# Sheet1.net
KiCad netlist of a schematic drawn in Altium Designer
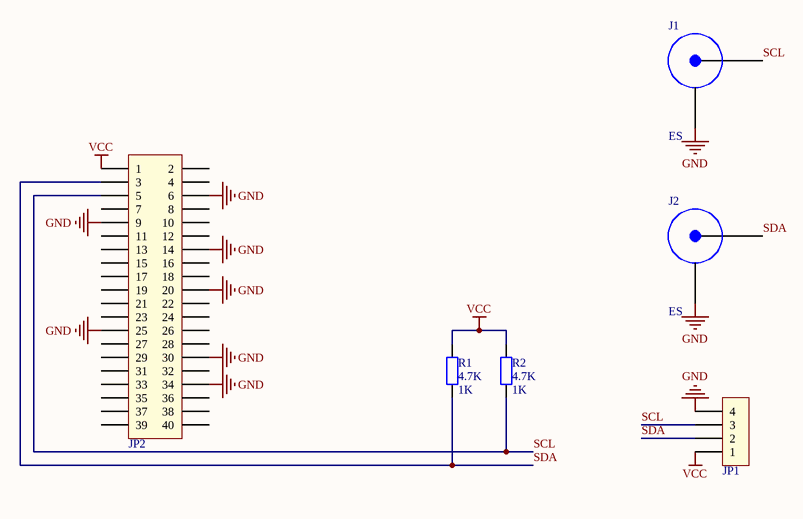
[diagram p0: Sheet1.SchDoc]

(export (version "E")
  (design (tool "Eeschema 10.0.6"))
  (components
    (comp (ref "J1") (value "ES") (footprint "BNC") (libsource (lib "Gamel_Trophy_v4re1") (part "BNC")))
    (comp (ref "J2") (value "ES") (footprint "BNC") (libsource (lib "Gamel_Trophy_v4re1") (part "BNC")))
    (comp (ref "JP1")
      (value "Connecteur Autocom 4pts")
      (footprint "Autocom HE14 - 4 - Coudé")
      (description "connecteur autocom HE14 4 pts")
      (fields
        (field (name "MANUFACTURER") "TE CONNECTIVITY / AMP")
        (field (name "MANUFACTURER PART NUMBER") "281698-4")
      )
      (libsource (lib "GEII") (part "Connecteur Autocom 4 pts"))
    )
    (comp (ref "JP2")
      (value "HE10 2x20")
      (footprint "HE10 2x20")
      (description "Header, 20-Pin, Dual row")
      (fields
        (field (name "MANUFACTURER") "HARTING")
        (field (name "MANUFACTURER PART NUMBER") "09 18 540 7324")
        (field (name "APPROVAL BODIES") "BT 224, BS 9525, F0023, NFC93-428 (HE10), MIL-C-83503, DIN 41651")
      )
      (libsource (lib "GEII") (part "HE10 2x20"))
    )
    (comp (ref "R1")
      (value "4.7K")
      (footprint "AXIAL-0.4")
      (description "Resistor")
      (fields (field (name "ALTIUM_VALUE") "1K") (field (name "PUBLISHER") "Altium Limited"))
      (libsource (lib "Miscellaneous Devices") (part "Res2"))
    )
    (comp (ref "R2")
      (value "4.7K")
      (footprint "AXIAL-0.4")
      (description "Resistor")
      (fields (field (name "ALTIUM_VALUE") "1K") (field (name "PUBLISHER") "Altium Limited"))
      (libsource (lib "Miscellaneous Devices") (part "Res2"))
    )
  )
  (nets
    (net (code "1") (name "/SCL") (class "Default")
      (node (ref "J1") (pin "1") (pinfunction "SIGNAL_1") (pintype "passive"))
      (node (ref "JP1") (pin "3") (pinfunction "3_3") (pintype "passive"))
      (node (ref "JP2") (pin "5") (pinfunction "5_5") (pintype "passive"))
      (node (ref "R2") (pin "1") (pinfunction "1_1") (pintype "passive"))
    )
    (net (code "2") (name "/SDA") (class "Default")
      (node (ref "J2") (pin "1") (pinfunction "SIGNAL_1") (pintype "passive"))
      (node (ref "JP1") (pin "2") (pinfunction "2_2") (pintype "passive"))
      (node (ref "JP2") (pin "3") (pinfunction "3_3") (pintype "passive"))
      (node (ref "R1") (pin "1") (pinfunction "1_1") (pintype "passive"))
    )
    (net (code "3") (name "GND") (class "Default")
      (node (ref "J1") (pin "2") (pinfunction "GND_2") (pintype "passive"))
      (node (ref "J2") (pin "2") (pinfunction "GND_2") (pintype "passive"))
      (node (ref "JP1") (pin "4") (pinfunction "4_4") (pintype "passive"))
      (node (ref "JP2") (pin "14") (pinfunction "14_14") (pintype "passive"))
      (node (ref "JP2") (pin "20") (pinfunction "20_20") (pintype "passive"))
      (node (ref "JP2") (pin "25") (pinfunction "25_25") (pintype "passive"))
      (node (ref "JP2") (pin "30") (pinfunction "30_30") (pintype "passive"))
      (node (ref "JP2") (pin "34") (pinfunction "34_34") (pintype "passive"))
      (node (ref "JP2") (pin "6") (pinfunction "6_6") (pintype "passive"))
      (node (ref "JP2") (pin "9") (pinfunction "9_9") (pintype "passive"))
    )
    (net (code "4") (name "VCC") (class "Default")
      (node (ref "JP1") (pin "1") (pinfunction "1_1") (pintype "passive"))
      (node (ref "JP2") (pin "1") (pinfunction "1_1") (pintype "passive"))
      (node (ref "R1") (pin "2") (pinfunction "2_2") (pintype "passive"))
      (node (ref "R2") (pin "2") (pinfunction "2_2") (pintype "passive"))
    )
    (net (code "5") (name "unconnected-(JP2-Pad2)") (class "Default")
      (node (ref "JP2") (pin "2") (pinfunction "2_2") (pintype "passive"))
    )
    (net (code "6") (name "unconnected-(JP2-Pad4)") (class "Default")
      (node (ref "JP2") (pin "4") (pinfunction "4_4") (pintype "passive"))
    )
    (net (code "7") (name "unconnected-(JP2-Pad7)") (class "Default")
      (node (ref "JP2") (pin "7") (pinfunction "7_7") (pintype "passive"))
    )
    (net (code "8") (name "unconnected-(JP2-Pad8)") (class "Default")
      (node (ref "JP2") (pin "8") (pinfunction "8_8") (pintype "passive"))
    )
    (net (code "9") (name "unconnected-(JP2-Pad10)") (class "Default")
      (node (ref "JP2") (pin "10") (pinfunction "10_10") (pintype "passive"))
    )
    (net (code "10") (name "unconnected-(JP2-Pad11)") (class "Default")
      (node (ref "JP2") (pin "11") (pinfunction "11_11") (pintype "passive"))
    )
    (net (code "11") (name "unconnected-(JP2-Pad12)") (class "Default")
      (node (ref "JP2") (pin "12") (pinfunction "12_12") (pintype "passive"))
    )
    (net (code "12") (name "unconnected-(JP2-Pad13)") (class "Default")
      (node (ref "JP2") (pin "13") (pinfunction "13_13") (pintype "passive"))
    )
    (net (code "13") (name "unconnected-(JP2-Pad15)") (class "Default")
      (node (ref "JP2") (pin "15") (pinfunction "15_15") (pintype "passive"))
    )
    (net (code "14") (name "unconnected-(JP2-Pad16)") (class "Default")
      (node (ref "JP2") (pin "16") (pinfunction "16_16") (pintype "passive"))
    )
    (net (code "15") (name "unconnected-(JP2-Pad17)") (class "Default")
      (node (ref "JP2") (pin "17") (pinfunction "17_17") (pintype "passive"))
    )
    (net (code "16") (name "unconnected-(JP2-Pad18)") (class "Default")
      (node (ref "JP2") (pin "18") (pinfunction "18_18") (pintype "passive"))
    )
    (net (code "17") (name "unconnected-(JP2-Pad19)") (class "Default")
      (node (ref "JP2") (pin "19") (pinfunction "19_19") (pintype "passive"))
    )
    (net (code "18") (name "unconnected-(JP2-Pad21)") (class "Default")
      (node (ref "JP2") (pin "21") (pinfunction "21_21") (pintype "passive"))
    )
    (net (code "19") (name "unconnected-(JP2-Pad22)") (class "Default")
      (node (ref "JP2") (pin "22") (pinfunction "22_22") (pintype "passive"))
    )
    (net (code "20") (name "unconnected-(JP2-Pad23)") (class "Default")
      (node (ref "JP2") (pin "23") (pinfunction "23_23") (pintype "passive"))
    )
    (net (code "21") (name "unconnected-(JP2-Pad24)") (class "Default")
      (node (ref "JP2") (pin "24") (pinfunction "24_24") (pintype "passive"))
    )
    (net (code "22") (name "unconnected-(JP2-Pad26)") (class "Default")
      (node (ref "JP2") (pin "26") (pinfunction "26_26") (pintype "passive"))
    )
    (net (code "23") (name "unconnected-(JP2-Pad27)") (class "Default")
      (node (ref "JP2") (pin "27") (pinfunction "27_27") (pintype "passive"))
    )
    (net (code "24") (name "unconnected-(JP2-Pad28)") (class "Default")
      (node (ref "JP2") (pin "28") (pinfunction "28_28") (pintype "passive"))
    )
    (net (code "25") (name "unconnected-(JP2-Pad29)") (class "Default")
      (node (ref "JP2") (pin "29") (pinfunction "29_29") (pintype "passive"))
    )
    (net (code "26") (name "unconnected-(JP2-Pad31)") (class "Default")
      (node (ref "JP2") (pin "31") (pinfunction "31_31") (pintype "passive"))
    )
    (net (code "27") (name "unconnected-(JP2-Pad32)") (class "Default")
      (node (ref "JP2") (pin "32") (pinfunction "32_32") (pintype "passive"))
    )
    (net (code "28") (name "unconnected-(JP2-Pad33)") (class "Default")
      (node (ref "JP2") (pin "33") (pinfunction "33_33") (pintype "passive"))
    )
    (net (code "29") (name "unconnected-(JP2-Pad35)") (class "Default")
      (node (ref "JP2") (pin "35") (pinfunction "35_35") (pintype "passive"))
    )
    (net (code "30") (name "unconnected-(JP2-Pad36)") (class "Default")
      (node (ref "JP2") (pin "36") (pinfunction "36_36") (pintype "passive"))
    )
    (net (code "31") (name "unconnected-(JP2-Pad37)") (class "Default")
      (node (ref "JP2") (pin "37") (pinfunction "37_37") (pintype "passive"))
    )
    (net (code "32") (name "unconnected-(JP2-Pad38)") (class "Default")
      (node (ref "JP2") (pin "38") (pinfunction "38_38") (pintype "passive"))
    )
    (net (code "33") (name "unconnected-(JP2-Pad39)") (class "Default")
      (node (ref "JP2") (pin "39") (pinfunction "39_39") (pintype "passive"))
    )
    (net (code "34") (name "unconnected-(JP2-Pad40)") (class "Default")
      (node (ref "JP2") (pin "40") (pinfunction "40_40") (pintype "passive"))
    )
  )
)
